# J533_harness.net
KiCad netlist of a schematic drawn in EAGLE
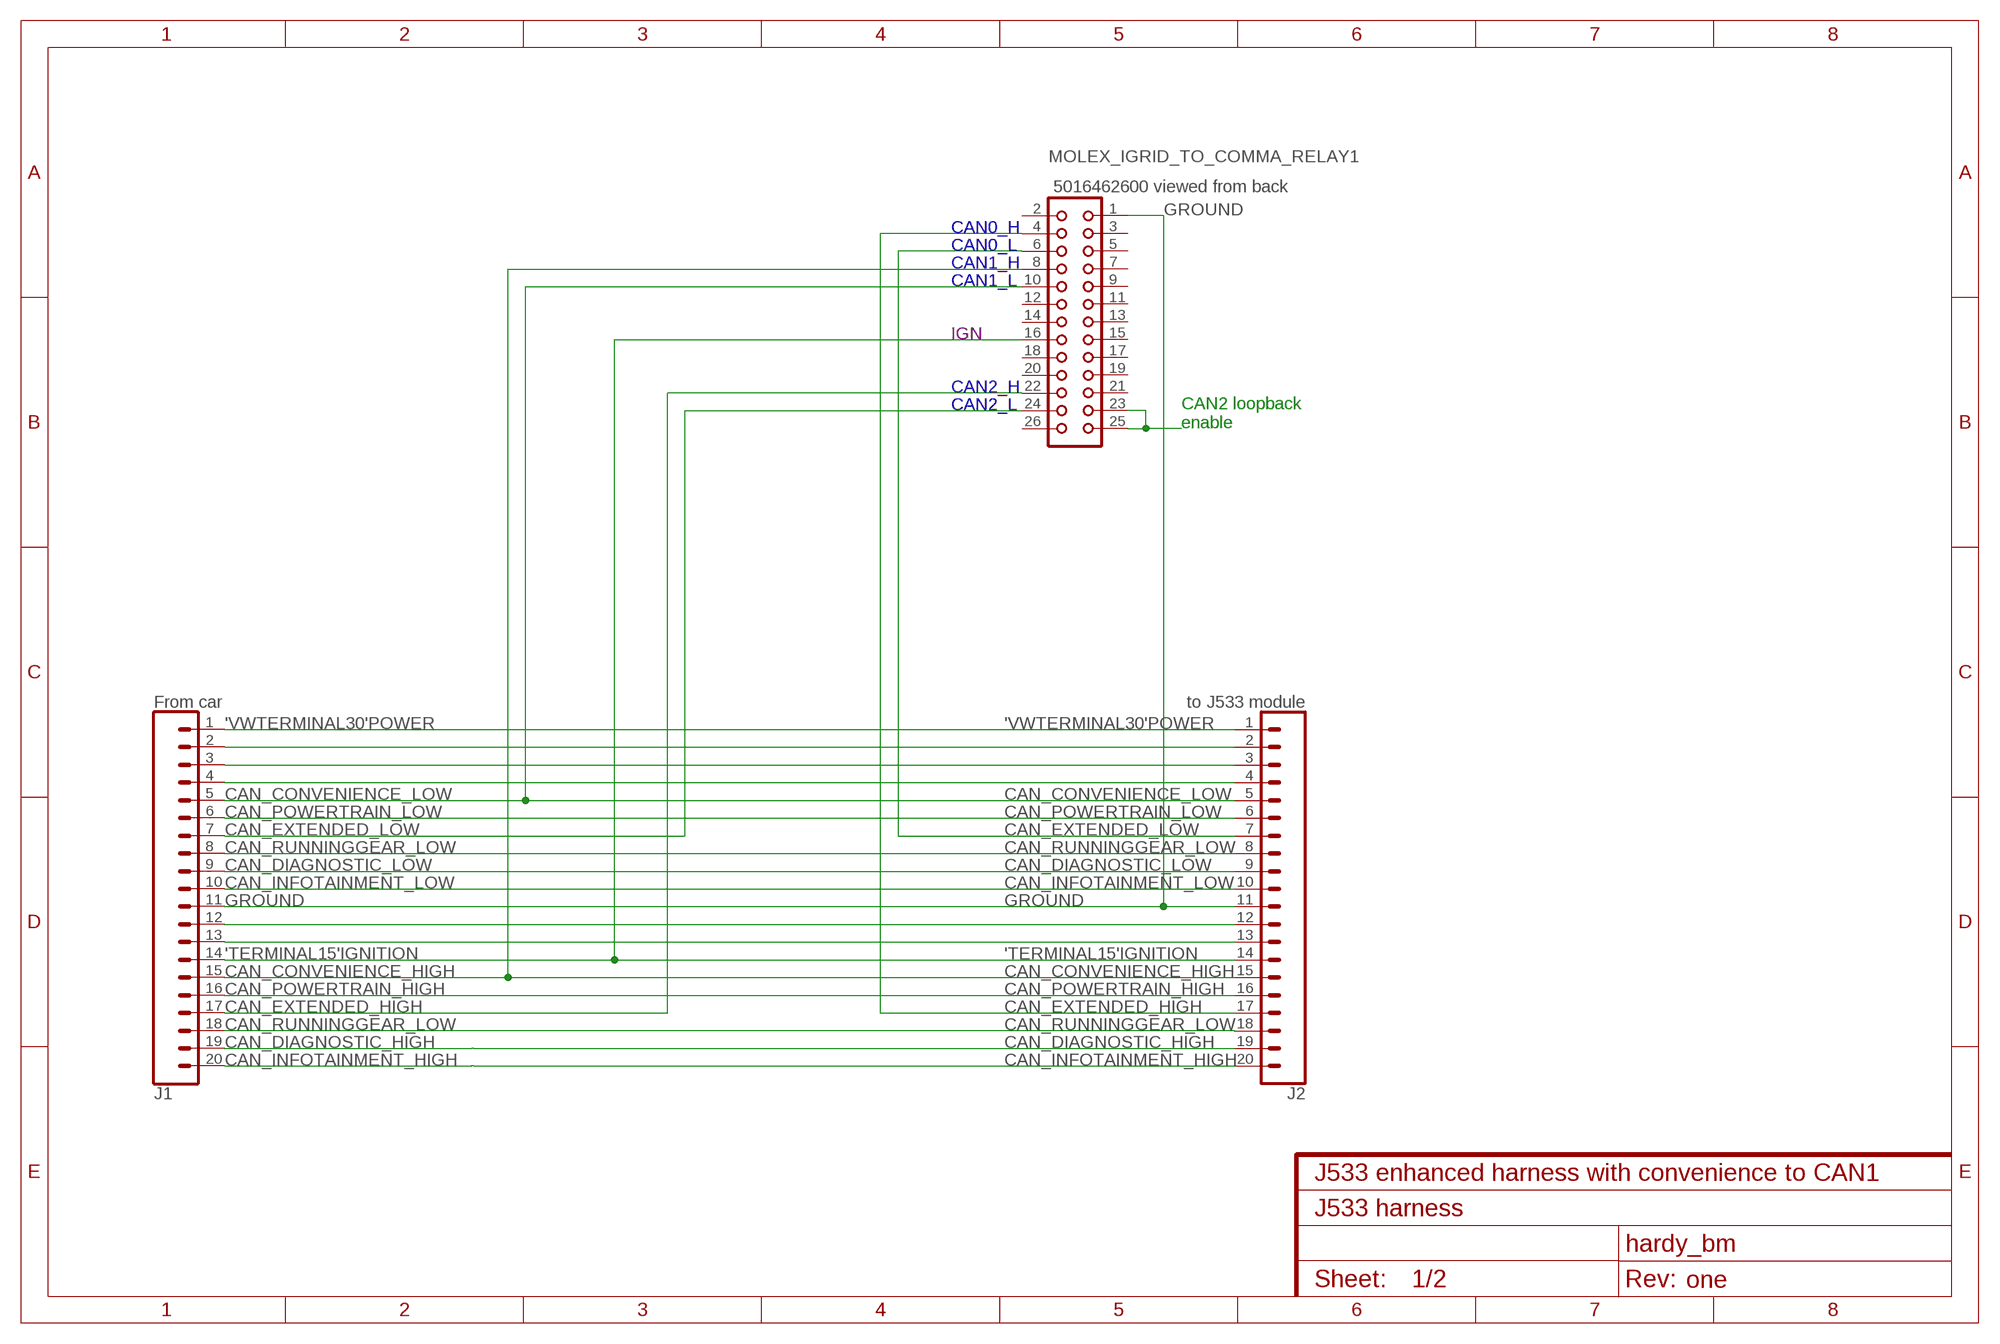
[diagram p0: schematic, sheet 1]
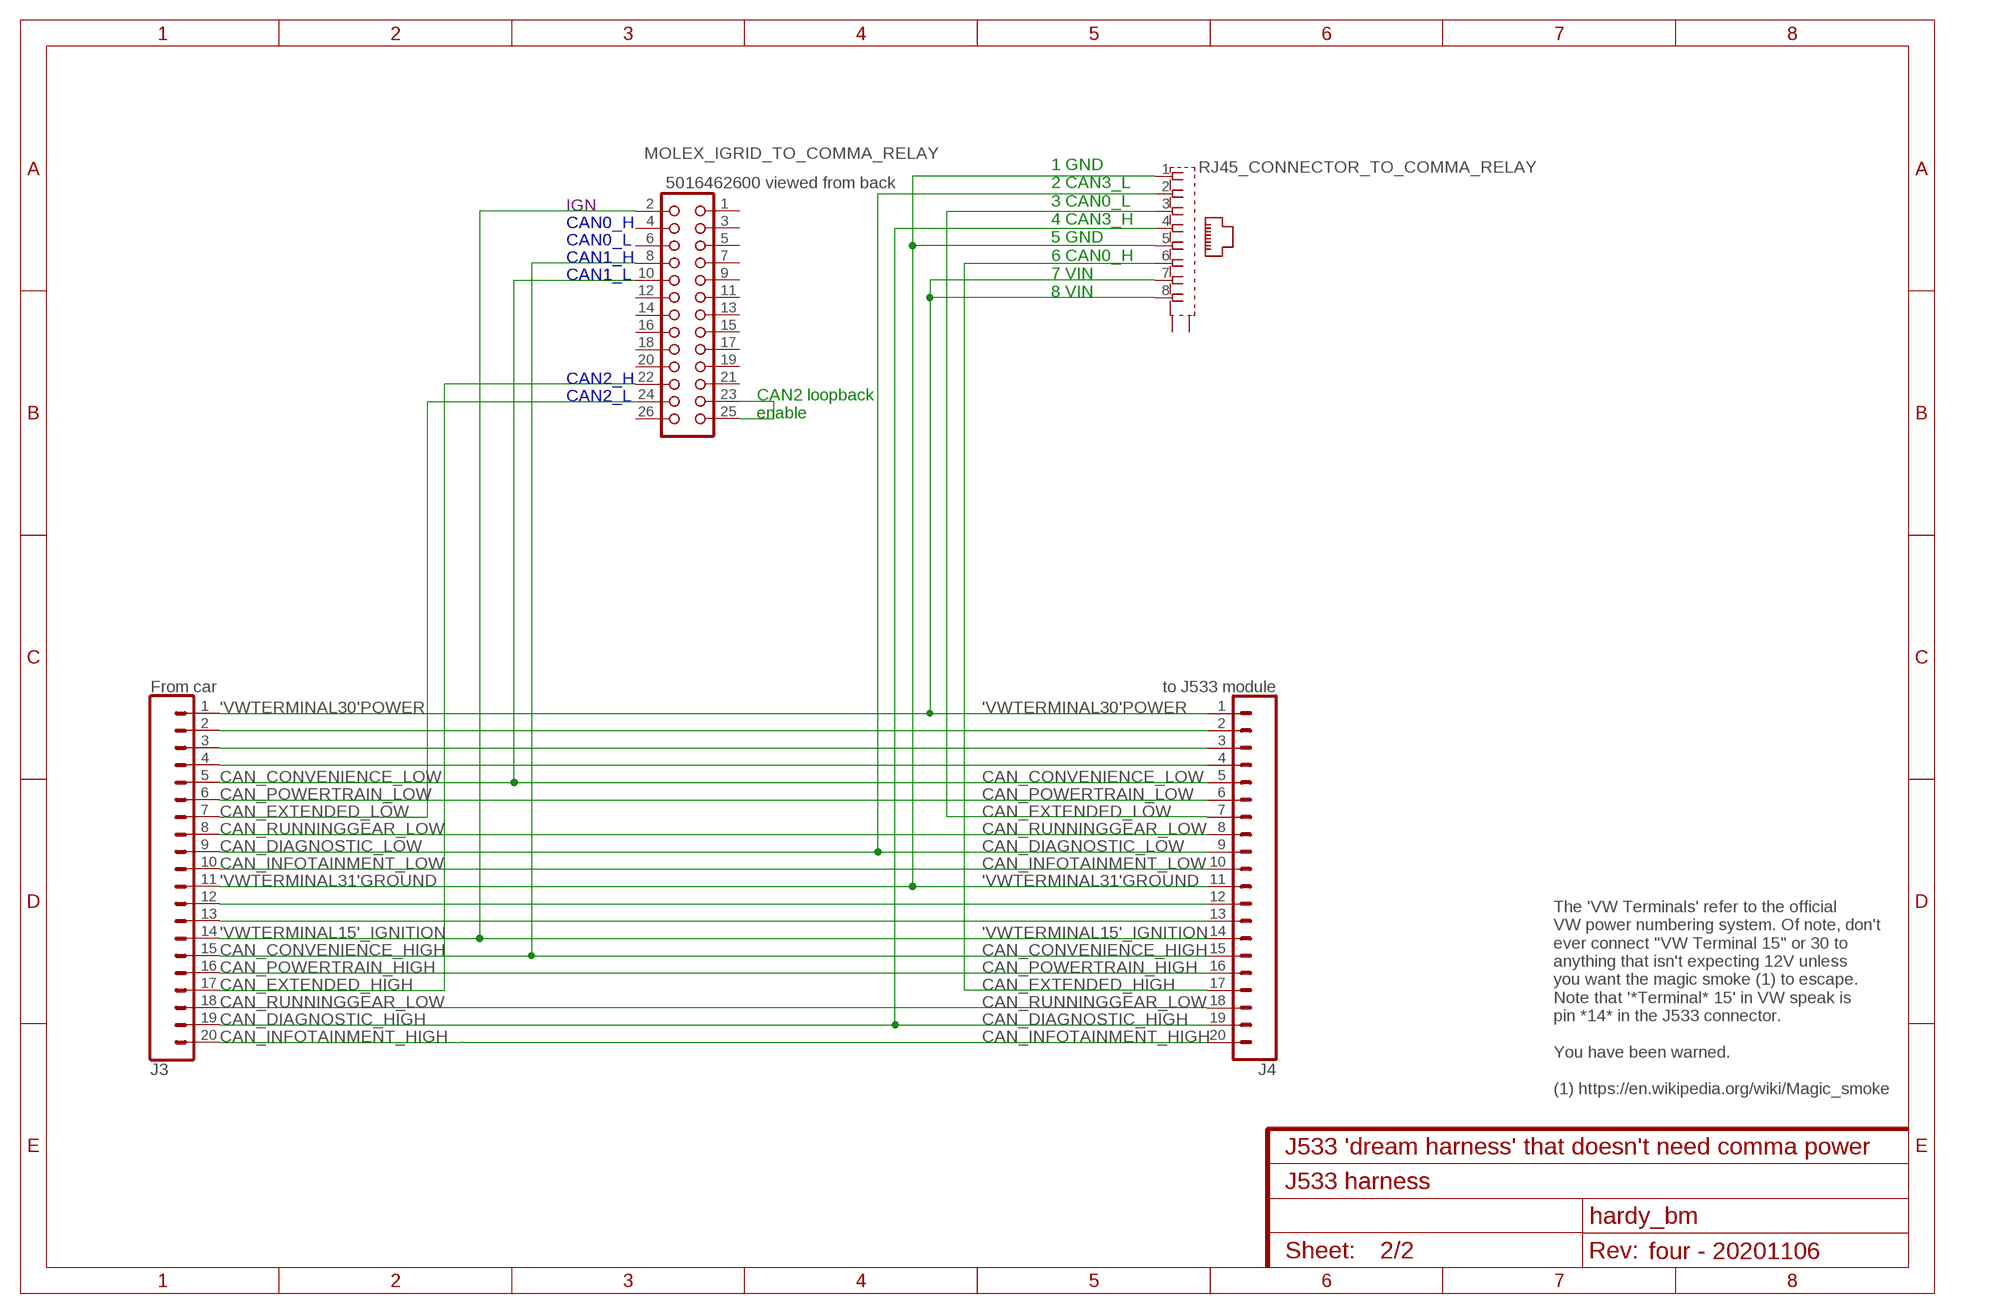
[diagram p1: schematic, sheet 2]

(export (version "E")
  (design (tool "Eeschema 10.0.6"))
  (components
    (comp (ref "J3")
      (value "From car")
      (footprint "eagle-import:1X20")
      (libsource (lib "eagle-import") (part "CONN_20"))
    )
    (comp (ref "J4")
      (value "to J533 module")
      (footprint "eagle-import:1X20")
      (libsource (lib "eagle-import") (part "CONN_20"))
    )
    (comp (ref "MOLEX_IGRID_TO_COMMA_RELAY")
      (value "5016462600 viewed from back")
      (footprint "eagle-import:CON26")
      (libsource (lib "eagle-import") (part "CON26"))
    )
    (comp (ref "RJ45_CONNECTOR_TO_COMMA_RELAY")
      (value "GLX-S-88M")
      (footprint "eagle-import:GLX-S-88M")
      (libsource (lib "eagle-import") (part "GLX-S-88M"))
    )
    (comp (ref "J1")
      (value "From car")
      (footprint "eagle-import:1X20")
      (libsource (lib "eagle-import") (part "CONN_20"))
    )
    (comp (ref "J2")
      (value "to J533 module")
      (footprint "eagle-import:1X20")
      (libsource (lib "eagle-import") (part "CONN_20"))
    )
    (comp (ref "MOLEX_IGRID_TO_COMMA_RELAY1")
      (value "5016462600 viewed from back")
      (footprint "eagle-import:CON26")
      (libsource (lib "eagle-import") (part "CON26"))
    )
  )
  (nets
    (net (code "1") (name "'TERMINAL15'IGNITION") (class "Default")
      (node (ref "J1") (pin "14") (pinfunction "14_14") (pintype "passive"))
      (node (ref "J2") (pin "14") (pinfunction "14_14") (pintype "passive"))
      (node (ref "MOLEX_IGRID_TO_COMMA_RELAY1") (pin "16") (pinfunction "16_16") (pintype "passive"))
    )
    (net (code "2") (name "'VWTERMINAL15'_IGNITION") (class "Default")
      (node (ref "J3") (pin "14") (pinfunction "14_14") (pintype "passive"))
      (node (ref "J4") (pin "14") (pinfunction "14_14") (pintype "passive"))
      (node (ref "MOLEX_IGRID_TO_COMMA_RELAY") (pin "2") (pinfunction "2_2") (pintype "passive"))
    )
    (net (code "3") (name "'VWTERMINAL30'POWER") (class "Default")
      (node (ref "J1") (pin "1") (pinfunction "1_1") (pintype "passive"))
      (node (ref "J2") (pin "1") (pinfunction "1_1") (pintype "passive"))
      (node (ref "J3") (pin "1") (pinfunction "1_1") (pintype "passive"))
      (node (ref "J4") (pin "1") (pinfunction "1_1") (pintype "passive"))
      (node (ref "RJ45_CONNECTOR_TO_COMMA_RELAY") (pin "7") (pinfunction "7_7") (pintype "passive"))
      (node (ref "RJ45_CONNECTOR_TO_COMMA_RELAY") (pin "8") (pinfunction "8_8") (pintype "passive"))
    )
    (net (code "4") (name "'VWTERMINAL31'GROUND") (class "Default")
      (node (ref "J3") (pin "11") (pinfunction "11_11") (pintype "passive"))
      (node (ref "J4") (pin "11") (pinfunction "11_11") (pintype "passive"))
      (node (ref "RJ45_CONNECTOR_TO_COMMA_RELAY") (pin "1") (pinfunction "1_1") (pintype "passive"))
      (node (ref "RJ45_CONNECTOR_TO_COMMA_RELAY") (pin "5") (pinfunction "5_5") (pintype "passive"))
    )
    (net (code "5") (name "CAN_CONVENIENCE_HIGH") (class "Default")
      (node (ref "J1") (pin "15") (pinfunction "15_15") (pintype "passive"))
      (node (ref "J2") (pin "15") (pinfunction "15_15") (pintype "passive"))
      (node (ref "J3") (pin "15") (pinfunction "15_15") (pintype "passive"))
      (node (ref "J4") (pin "15") (pinfunction "15_15") (pintype "passive"))
      (node (ref "MOLEX_IGRID_TO_COMMA_RELAY") (pin "8") (pinfunction "8_8") (pintype "passive"))
      (node (ref "MOLEX_IGRID_TO_COMMA_RELAY1") (pin "8") (pinfunction "8_8") (pintype "passive"))
    )
    (net (code "6") (name "CAN_CONVENIENCE_LOW") (class "Default")
      (node (ref "J1") (pin "5") (pinfunction "5_5") (pintype "passive"))
      (node (ref "J2") (pin "5") (pinfunction "5_5") (pintype "passive"))
      (node (ref "J3") (pin "5") (pinfunction "5_5") (pintype "passive"))
      (node (ref "J4") (pin "5") (pinfunction "5_5") (pintype "passive"))
      (node (ref "MOLEX_IGRID_TO_COMMA_RELAY") (pin "10") (pinfunction "10_10") (pintype "passive"))
      (node (ref "MOLEX_IGRID_TO_COMMA_RELAY1") (pin "10") (pinfunction "10_10") (pintype "passive"))
    )
    (net (code "7") (name "CAN_DIAGNOSTIC_HIGH") (class "Default")
      (node (ref "J1") (pin "19") (pinfunction "19_19") (pintype "passive"))
      (node (ref "J2") (pin "19") (pinfunction "19_19") (pintype "passive"))
      (node (ref "J3") (pin "19") (pinfunction "19_19") (pintype "passive"))
      (node (ref "J4") (pin "19") (pinfunction "19_19") (pintype "passive"))
      (node (ref "RJ45_CONNECTOR_TO_COMMA_RELAY") (pin "4") (pinfunction "4_4") (pintype "passive"))
    )
    (net (code "8") (name "CAN_DIAGNOSTIC_LOW") (class "Default")
      (node (ref "J1") (pin "9") (pinfunction "9_9") (pintype "passive"))
      (node (ref "J2") (pin "9") (pinfunction "9_9") (pintype "passive"))
      (node (ref "J3") (pin "9") (pinfunction "9_9") (pintype "passive"))
      (node (ref "J4") (pin "9") (pinfunction "9_9") (pintype "passive"))
      (node (ref "RJ45_CONNECTOR_TO_COMMA_RELAY") (pin "2") (pinfunction "2_2") (pintype "passive"))
    )
    (net (code "9") (name "CAN_EXTENDED_HIGH") (class "Default")
      (node (ref "J1") (pin "17") (pinfunction "17_17") (pintype "passive"))
      (node (ref "J3") (pin "17") (pinfunction "17_17") (pintype "passive"))
      (node (ref "MOLEX_IGRID_TO_COMMA_RELAY") (pin "22") (pinfunction "22_22") (pintype "passive"))
      (node (ref "MOLEX_IGRID_TO_COMMA_RELAY1") (pin "22") (pinfunction "22_22") (pintype "passive"))
    )
    (net (code "10") (name "CAN_EXTENDED_LOW") (class "Default")
      (node (ref "J1") (pin "7") (pinfunction "7_7") (pintype "passive"))
      (node (ref "J3") (pin "7") (pinfunction "7_7") (pintype "passive"))
      (node (ref "MOLEX_IGRID_TO_COMMA_RELAY") (pin "24") (pinfunction "24_24") (pintype "passive"))
      (node (ref "MOLEX_IGRID_TO_COMMA_RELAY1") (pin "24") (pinfunction "24_24") (pintype "passive"))
    )
    (net (code "11") (name "CAN_INFOTAINMENT_HIGH") (class "Default")
      (node (ref "J1") (pin "20") (pinfunction "20_20") (pintype "passive"))
      (node (ref "J2") (pin "20") (pinfunction "20_20") (pintype "passive"))
      (node (ref "J3") (pin "20") (pinfunction "20_20") (pintype "passive"))
      (node (ref "J4") (pin "20") (pinfunction "20_20") (pintype "passive"))
    )
    (net (code "12") (name "CAN_INFOTAINMENT_LOW") (class "Default")
      (node (ref "J1") (pin "10") (pinfunction "10_10") (pintype "passive"))
      (node (ref "J2") (pin "10") (pinfunction "10_10") (pintype "passive"))
      (node (ref "J3") (pin "10") (pinfunction "10_10") (pintype "passive"))
      (node (ref "J4") (pin "10") (pinfunction "10_10") (pintype "passive"))
    )
    (net (code "13") (name "CAN_POWERTRAIN_HIGH") (class "Default")
      (node (ref "J1") (pin "16") (pinfunction "16_16") (pintype "passive"))
      (node (ref "J2") (pin "16") (pinfunction "16_16") (pintype "passive"))
      (node (ref "J3") (pin "16") (pinfunction "16_16") (pintype "passive"))
      (node (ref "J4") (pin "16") (pinfunction "16_16") (pintype "passive"))
    )
    (net (code "14") (name "CAN_POWERTRAIN_LOW") (class "Default")
      (node (ref "J1") (pin "6") (pinfunction "6_6") (pintype "passive"))
      (node (ref "J2") (pin "6") (pinfunction "6_6") (pintype "passive"))
      (node (ref "J3") (pin "6") (pinfunction "6_6") (pintype "passive"))
      (node (ref "J4") (pin "6") (pinfunction "6_6") (pintype "passive"))
    )
    (net (code "15") (name "CAN_RUNNINGGEAR_LOW") (class "Default")
      (node (ref "J1") (pin "18") (pinfunction "18_18") (pintype "passive"))
      (node (ref "J1") (pin "8") (pinfunction "8_8") (pintype "passive"))
      (node (ref "J2") (pin "18") (pinfunction "18_18") (pintype "passive"))
      (node (ref "J2") (pin "8") (pinfunction "8_8") (pintype "passive"))
      (node (ref "J3") (pin "18") (pinfunction "18_18") (pintype "passive"))
      (node (ref "J3") (pin "8") (pinfunction "8_8") (pintype "passive"))
      (node (ref "J4") (pin "18") (pinfunction "18_18") (pintype "passive"))
      (node (ref "J4") (pin "8") (pinfunction "8_8") (pintype "passive"))
    )
    (net (code "16") (name "GROUND") (class "Default")
      (node (ref "J1") (pin "11") (pinfunction "11_11") (pintype "passive"))
      (node (ref "J2") (pin "11") (pinfunction "11_11") (pintype "passive"))
      (node (ref "MOLEX_IGRID_TO_COMMA_RELAY1") (pin "1") (pinfunction "1_1") (pintype "passive"))
    )
    (net (code "17") (name "GROUND_IN_MQB_ONLY_DONT_RELY_ON_IT") (class "Default")
      (node (ref "J1") (pin "12") (pinfunction "12_12") (pintype "passive"))
      (node (ref "J2") (pin "12") (pinfunction "12_12") (pintype "passive"))
      (node (ref "J3") (pin "12") (pinfunction "12_12") (pintype "passive"))
      (node (ref "J4") (pin "12") (pinfunction "12_12") (pintype "passive"))
    )
    (net (code "18") (name "J367LINBUS") (class "Default")
      (node (ref "J3") (pin "13") (pinfunction "13_13") (pintype "passive"))
      (node (ref "J3") (pin "3") (pinfunction "3_3") (pintype "passive"))
      (node (ref "J4") (pin "13") (pinfunction "13_13") (pintype "passive"))
      (node (ref "J4") (pin "3") (pinfunction "3_3") (pintype "passive"))
    )
    (net (code "19") (name "NOT_USED") (class "Default")
      (node (ref "J1") (pin "4") (pinfunction "4_4") (pintype "passive"))
      (node (ref "J2") (pin "4") (pinfunction "4_4") (pintype "passive"))
      (node (ref "J3") (pin "4") (pinfunction "4_4") (pintype "passive"))
      (node (ref "J4") (pin "4") (pinfunction "4_4") (pintype "passive"))
    )
    (net (code "20") (name "Net-(J1-Pad2)") (class "Default")
      (node (ref "J1") (pin "2") (pinfunction "2_2") (pintype "passive"))
      (node (ref "J2") (pin "2") (pinfunction "2_2") (pintype "passive"))
    )
    (net (code "21") (name "Net-(J1-Pad3)") (class "Default")
      (node (ref "J1") (pin "3") (pinfunction "3_3") (pintype "passive"))
      (node (ref "J2") (pin "3") (pinfunction "3_3") (pintype "passive"))
    )
    (net (code "22") (name "Net-(J1-Pad13)") (class "Default")
      (node (ref "J1") (pin "13") (pinfunction "13_13") (pintype "passive"))
      (node (ref "J2") (pin "13") (pinfunction "13_13") (pintype "passive"))
    )
    (net (code "23") (name "Net-(J2-Pad7)") (class "Default")
      (node (ref "J2") (pin "7") (pinfunction "7_7") (pintype "passive"))
      (node (ref "MOLEX_IGRID_TO_COMMA_RELAY1") (pin "6") (pinfunction "6_6") (pintype "passive"))
    )
    (net (code "24") (name "Net-(J2-Pad17)") (class "Default")
      (node (ref "J2") (pin "17") (pinfunction "17_17") (pintype "passive"))
      (node (ref "MOLEX_IGRID_TO_COMMA_RELAY1") (pin "4") (pinfunction "4_4") (pintype "passive"))
    )
    (net (code "25") (name "Net-(J3-Pad2)") (class "Default")
      (node (ref "J3") (pin "2") (pinfunction "2_2") (pintype "passive"))
      (node (ref "J4") (pin "2") (pinfunction "2_2") (pintype "passive"))
    )
    (net (code "26") (name "Net-(J4-Pad7)") (class "Default")
      (node (ref "J4") (pin "7") (pinfunction "7_7") (pintype "passive"))
      (node (ref "RJ45_CONNECTOR_TO_COMMA_RELAY") (pin "3") (pinfunction "3_3") (pintype "passive"))
    )
    (net (code "27") (name "Net-(J4-Pad17)") (class "Default")
      (node (ref "J4") (pin "17") (pinfunction "17_17") (pintype "passive"))
      (node (ref "RJ45_CONNECTOR_TO_COMMA_RELAY") (pin "6") (pinfunction "6_6") (pintype "passive"))
    )
    (net (code "28") (name "Net-(MOLEX_IGRID_TO_COMMA_RELAY-Pad23)") (class "Default")
      (node (ref "MOLEX_IGRID_TO_COMMA_RELAY") (pin "23") (pinfunction "23_23") (pintype "passive"))
      (node (ref "MOLEX_IGRID_TO_COMMA_RELAY") (pin "25") (pinfunction "25_25") (pintype "passive"))
    )
    (net (code "29") (name "Net-(MOLEX_IGRID_TO_COMMA_RELAY1-Pad23)") (class "Default")
      (node (ref "MOLEX_IGRID_TO_COMMA_RELAY1") (pin "23") (pinfunction "23_23") (pintype "passive"))
      (node (ref "MOLEX_IGRID_TO_COMMA_RELAY1") (pin "25") (pinfunction "25_25") (pintype "passive"))
    )
    (net (code "30") (name "unconnected-(MOLEX_IGRID_TO_COMMA_RELAY-Pad1)") (class "Default")
      (node (ref "MOLEX_IGRID_TO_COMMA_RELAY") (pin "1") (pinfunction "1_1") (pintype "passive"))
    )
    (net (code "31") (name "unconnected-(MOLEX_IGRID_TO_COMMA_RELAY-Pad3)") (class "Default")
      (node (ref "MOLEX_IGRID_TO_COMMA_RELAY") (pin "3") (pinfunction "3_3") (pintype "passive"))
    )
    (net (code "32") (name "unconnected-(MOLEX_IGRID_TO_COMMA_RELAY-Pad4)") (class "Default")
      (node (ref "MOLEX_IGRID_TO_COMMA_RELAY") (pin "4") (pinfunction "4_4") (pintype "passive"))
    )
    (net (code "33") (name "unconnected-(MOLEX_IGRID_TO_COMMA_RELAY-Pad5)") (class "Default")
      (node (ref "MOLEX_IGRID_TO_COMMA_RELAY") (pin "5") (pinfunction "5_5") (pintype "passive"))
    )
    (net (code "34") (name "unconnected-(MOLEX_IGRID_TO_COMMA_RELAY-Pad6)") (class "Default")
      (node (ref "MOLEX_IGRID_TO_COMMA_RELAY") (pin "6") (pinfunction "6_6") (pintype "passive"))
    )
    (net (code "35") (name "unconnected-(MOLEX_IGRID_TO_COMMA_RELAY-Pad7)") (class "Default")
      (node (ref "MOLEX_IGRID_TO_COMMA_RELAY") (pin "7") (pinfunction "7_7") (pintype "passive"))
    )
    (net (code "36") (name "unconnected-(MOLEX_IGRID_TO_COMMA_RELAY-Pad9)") (class "Default")
      (node (ref "MOLEX_IGRID_TO_COMMA_RELAY") (pin "9") (pinfunction "9_9") (pintype "passive"))
    )
    (net (code "37") (name "unconnected-(MOLEX_IGRID_TO_COMMA_RELAY-Pad11)") (class "Default")
      (node (ref "MOLEX_IGRID_TO_COMMA_RELAY") (pin "11") (pinfunction "11_11") (pintype "passive"))
    )
    (net (code "38") (name "unconnected-(MOLEX_IGRID_TO_COMMA_RELAY-Pad12)") (class "Default")
      (node (ref "MOLEX_IGRID_TO_COMMA_RELAY") (pin "12") (pinfunction "12_12") (pintype "passive"))
    )
    (net (code "39") (name "unconnected-(MOLEX_IGRID_TO_COMMA_RELAY-Pad13)") (class "Default")
      (node (ref "MOLEX_IGRID_TO_COMMA_RELAY") (pin "13") (pinfunction "13_13") (pintype "passive"))
    )
    (net (code "40") (name "unconnected-(MOLEX_IGRID_TO_COMMA_RELAY-Pad14)") (class "Default")
      (node (ref "MOLEX_IGRID_TO_COMMA_RELAY") (pin "14") (pinfunction "14_14") (pintype "passive"))
    )
    (net (code "41") (name "unconnected-(MOLEX_IGRID_TO_COMMA_RELAY-Pad15)") (class "Default")
      (node (ref "MOLEX_IGRID_TO_COMMA_RELAY") (pin "15") (pinfunction "15_15") (pintype "passive"))
    )
    (net (code "42") (name "unconnected-(MOLEX_IGRID_TO_COMMA_RELAY-Pad16)") (class "Default")
      (node (ref "MOLEX_IGRID_TO_COMMA_RELAY") (pin "16") (pinfunction "16_16") (pintype "passive"))
    )
    (net (code "43") (name "unconnected-(MOLEX_IGRID_TO_COMMA_RELAY-Pad17)") (class "Default")
      (node (ref "MOLEX_IGRID_TO_COMMA_RELAY") (pin "17") (pinfunction "17_17") (pintype "passive"))
    )
    (net (code "44") (name "unconnected-(MOLEX_IGRID_TO_COMMA_RELAY-Pad18)") (class "Default")
      (node (ref "MOLEX_IGRID_TO_COMMA_RELAY") (pin "18") (pinfunction "18_18") (pintype "passive"))
    )
    (net (code "45") (name "unconnected-(MOLEX_IGRID_TO_COMMA_RELAY-Pad19)") (class "Default")
      (node (ref "MOLEX_IGRID_TO_COMMA_RELAY") (pin "19") (pinfunction "19_19") (pintype "passive"))
    )
    (net (code "46") (name "unconnected-(MOLEX_IGRID_TO_COMMA_RELAY-Pad20)") (class "Default")
      (node (ref "MOLEX_IGRID_TO_COMMA_RELAY") (pin "20") (pinfunction "20_20") (pintype "passive"))
    )
    (net (code "47") (name "unconnected-(MOLEX_IGRID_TO_COMMA_RELAY-Pad21)") (class "Default")
      (node (ref "MOLEX_IGRID_TO_COMMA_RELAY") (pin "21") (pinfunction "21_21") (pintype "passive"))
    )
    (net (code "48") (name "unconnected-(MOLEX_IGRID_TO_COMMA_RELAY-Pad26)") (class "Default")
      (node (ref "MOLEX_IGRID_TO_COMMA_RELAY") (pin "26") (pinfunction "26_26") (pintype "passive"))
    )
    (net (code "49") (name "unconnected-(MOLEX_IGRID_TO_COMMA_RELAY1-Pad2)") (class "Default")
      (node (ref "MOLEX_IGRID_TO_COMMA_RELAY1") (pin "2") (pinfunction "2_2") (pintype "passive"))
    )
    (net (code "50") (name "unconnected-(MOLEX_IGRID_TO_COMMA_RELAY1-Pad3)") (class "Default")
      (node (ref "MOLEX_IGRID_TO_COMMA_RELAY1") (pin "3") (pinfunction "3_3") (pintype "passive"))
    )
    (net (code "51") (name "unconnected-(MOLEX_IGRID_TO_COMMA_RELAY1-Pad5)") (class "Default")
      (node (ref "MOLEX_IGRID_TO_COMMA_RELAY1") (pin "5") (pinfunction "5_5") (pintype "passive"))
    )
    (net (code "52") (name "unconnected-(MOLEX_IGRID_TO_COMMA_RELAY1-Pad7)") (class "Default")
      (node (ref "MOLEX_IGRID_TO_COMMA_RELAY1") (pin "7") (pinfunction "7_7") (pintype "passive"))
    )
    (net (code "53") (name "unconnected-(MOLEX_IGRID_TO_COMMA_RELAY1-Pad9)") (class "Default")
      (node (ref "MOLEX_IGRID_TO_COMMA_RELAY1") (pin "9") (pinfunction "9_9") (pintype "passive"))
    )
    (net (code "54") (name "unconnected-(MOLEX_IGRID_TO_COMMA_RELAY1-Pad11)") (class "Default")
      (node (ref "MOLEX_IGRID_TO_COMMA_RELAY1") (pin "11") (pinfunction "11_11") (pintype "passive"))
    )
    (net (code "55") (name "unconnected-(MOLEX_IGRID_TO_COMMA_RELAY1-Pad12)") (class "Default")
      (node (ref "MOLEX_IGRID_TO_COMMA_RELAY1") (pin "12") (pinfunction "12_12") (pintype "passive"))
    )
    (net (code "56") (name "unconnected-(MOLEX_IGRID_TO_COMMA_RELAY1-Pad13)") (class "Default")
      (node (ref "MOLEX_IGRID_TO_COMMA_RELAY1") (pin "13") (pinfunction "13_13") (pintype "passive"))
    )
    (net (code "57") (name "unconnected-(MOLEX_IGRID_TO_COMMA_RELAY1-Pad14)") (class "Default")
      (node (ref "MOLEX_IGRID_TO_COMMA_RELAY1") (pin "14") (pinfunction "14_14") (pintype "passive"))
    )
    (net (code "58") (name "unconnected-(MOLEX_IGRID_TO_COMMA_RELAY1-Pad15)") (class "Default")
      (node (ref "MOLEX_IGRID_TO_COMMA_RELAY1") (pin "15") (pinfunction "15_15") (pintype "passive"))
    )
    (net (code "59") (name "unconnected-(MOLEX_IGRID_TO_COMMA_RELAY1-Pad17)") (class "Default")
      (node (ref "MOLEX_IGRID_TO_COMMA_RELAY1") (pin "17") (pinfunction "17_17") (pintype "passive"))
    )
    (net (code "60") (name "unconnected-(MOLEX_IGRID_TO_COMMA_RELAY1-Pad18)") (class "Default")
      (node (ref "MOLEX_IGRID_TO_COMMA_RELAY1") (pin "18") (pinfunction "18_18") (pintype "passive"))
    )
    (net (code "61") (name "unconnected-(MOLEX_IGRID_TO_COMMA_RELAY1-Pad19)") (class "Default")
      (node (ref "MOLEX_IGRID_TO_COMMA_RELAY1") (pin "19") (pinfunction "19_19") (pintype "passive"))
    )
    (net (code "62") (name "unconnected-(MOLEX_IGRID_TO_COMMA_RELAY1-Pad20)") (class "Default")
      (node (ref "MOLEX_IGRID_TO_COMMA_RELAY1") (pin "20") (pinfunction "20_20") (pintype "passive"))
    )
    (net (code "63") (name "unconnected-(MOLEX_IGRID_TO_COMMA_RELAY1-Pad21)") (class "Default")
      (node (ref "MOLEX_IGRID_TO_COMMA_RELAY1") (pin "21") (pinfunction "21_21") (pintype "passive"))
    )
    (net (code "64") (name "unconnected-(MOLEX_IGRID_TO_COMMA_RELAY1-Pad26)") (class "Default")
      (node (ref "MOLEX_IGRID_TO_COMMA_RELAY1") (pin "26") (pinfunction "26_26") (pintype "passive"))
    )
    (net (code "65") (name "unconnected-(RJ45_CONNECTOR_TO_COMMA_RELAY-PadS1)") (class "Default")
      (node (ref "RJ45_CONNECTOR_TO_COMMA_RELAY") (pin "S1") (pinfunction "S1_S1") (pintype "passive"))
    )
    (net (code "66") (name "unconnected-(RJ45_CONNECTOR_TO_COMMA_RELAY-PadS2)") (class "Default")
      (node (ref "RJ45_CONNECTOR_TO_COMMA_RELAY") (pin "S2") (pinfunction "S2_S2") (pintype "passive"))
    )
  )
)
